# FOTA_MicroController.net
KiCad netlist of a schematic drawn in Altium Designer
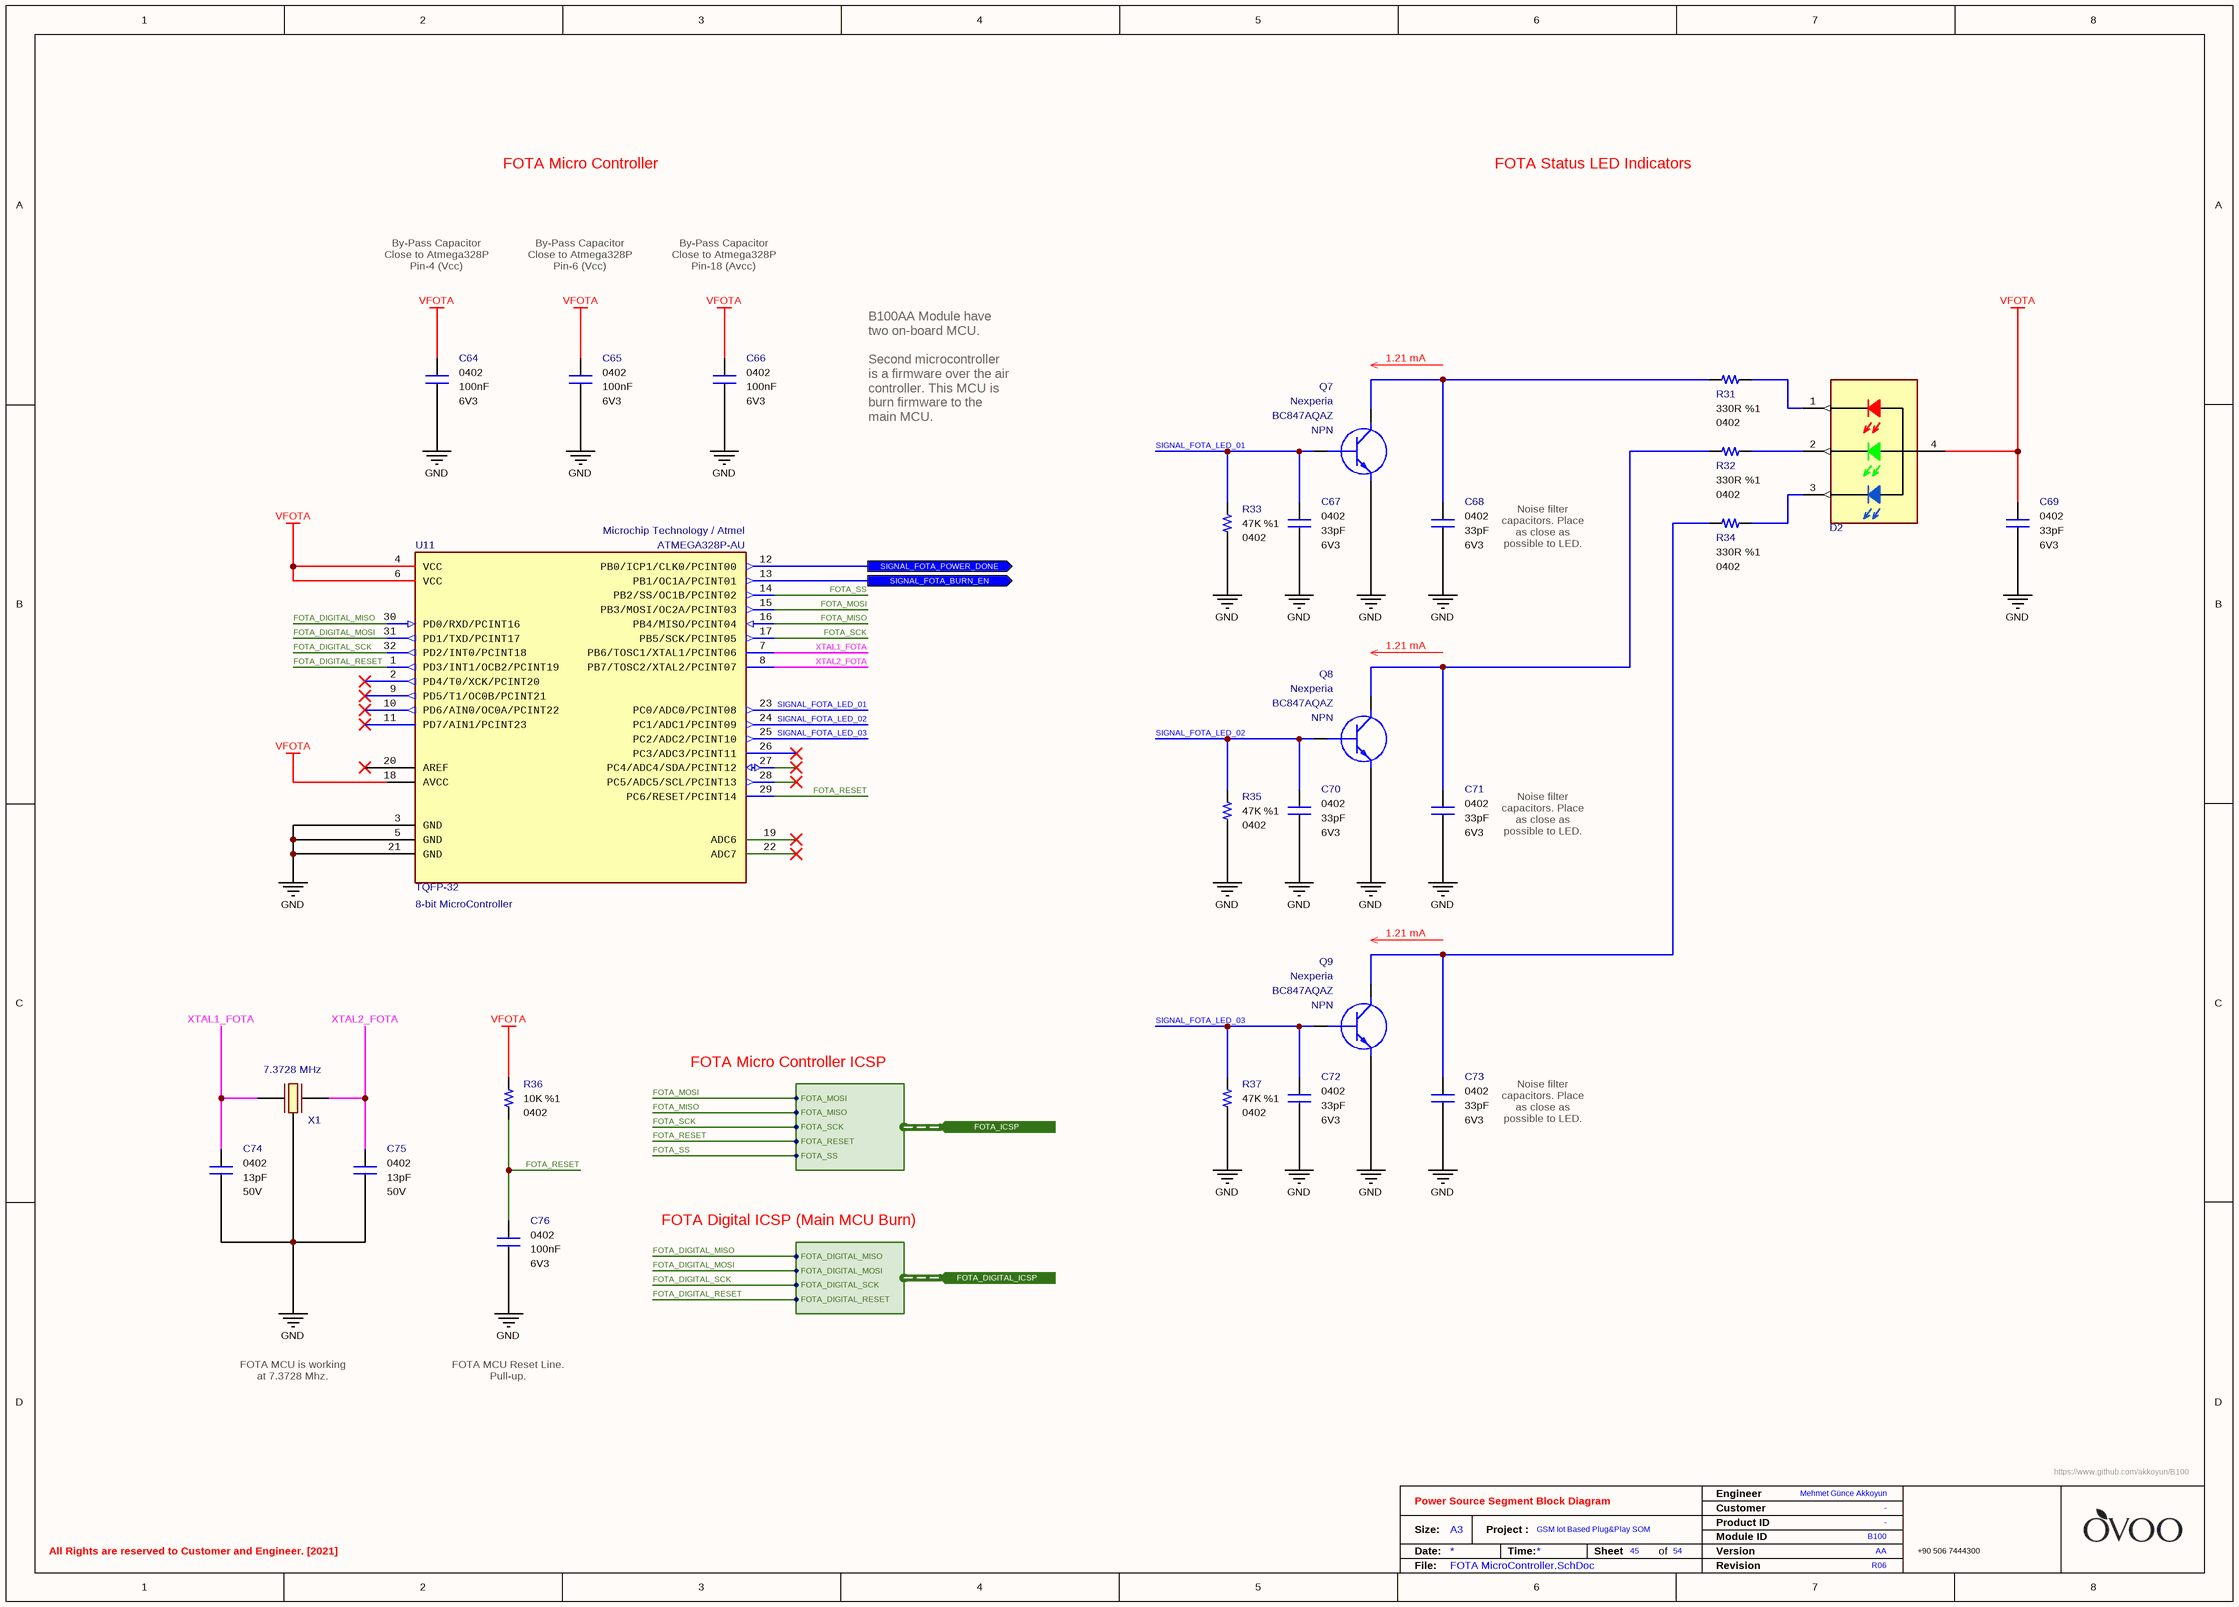
[diagram p0: FOTA MicroController.SchDoc]

(export (version "E")
  (design (tool "Eeschema 10.0.6"))
  (components
    (comp (ref "C64")
      (value "100nF")
      (footprint "CAPACITOR_0402")
      (description "Capacitor - 100nF [0402-6V3] (Ceramic)")
      (fields
        (field (name "TOLERANCE") "%10")
        (field (name "CASE") "0402")
        (field (name "VOLTAGE") "6V3")
        (field (name "MANUFACTURER PART NUMBER") "04026D104KAT4A")
      )
      (libsource (lib "Ovoo_Library") (part "Capacitor - 100nF [0402-6V3]"))
    )
    (comp (ref "C65")
      (value "100nF")
      (footprint "CAPACITOR_0402")
      (description "Capacitor - 100nF [0402-6V3] (Ceramic)")
      (fields
        (field (name "TOLERANCE") "%10")
        (field (name "CASE") "0402")
        (field (name "VOLTAGE") "6V3")
        (field (name "MANUFACTURER PART NUMBER") "04026D104KAT4A")
      )
      (libsource (lib "Ovoo_Library") (part "Capacitor - 100nF [0402-6V3]"))
    )
    (comp (ref "C66")
      (value "100nF")
      (footprint "CAPACITOR_0402")
      (description "Capacitor - 100nF [0402-6V3] (Ceramic)")
      (fields
        (field (name "TOLERANCE") "%10")
        (field (name "CASE") "0402")
        (field (name "VOLTAGE") "6V3")
        (field (name "MANUFACTURER PART NUMBER") "04026D104KAT4A")
      )
      (libsource (lib "Ovoo_Library") (part "Capacitor - 100nF [0402-6V3]"))
    )
    (comp (ref "C67")
      (value "33pF")
      (footprint "CAPACITOR_0402")
      (description "Capacitor - 33pF [0402] (Ceramic)")
      (fields
        (field (name "CASE") "0402")
        (field (name "TOLERANCE") "10%")
        (field (name "VOLTAGE") "6V3")
        (field (name "MANUFACTURER PART NUMBER") "C0402C330J9RACAUTO")
      )
      (libsource (lib "Ovoo_Library") (part "Capacitor - 33pF [0402-6V3]"))
    )
    (comp (ref "C68")
      (value "33pF")
      (footprint "CAPACITOR_0402")
      (description "Capacitor - 33pF [0402] (Ceramic)")
      (fields
        (field (name "CASE") "0402")
        (field (name "TOLERANCE") "10%")
        (field (name "VOLTAGE") "6V3")
        (field (name "MANUFACTURER PART NUMBER") "C0402C330J9RACAUTO")
      )
      (libsource (lib "Ovoo_Library") (part "Capacitor - 33pF [0402-6V3]"))
    )
    (comp (ref "C69")
      (value "33pF")
      (footprint "CAPACITOR_0402")
      (description "Capacitor - 33pF [0402] (Ceramic)")
      (fields
        (field (name "CASE") "0402")
        (field (name "TOLERANCE") "10%")
        (field (name "VOLTAGE") "6V3")
        (field (name "MANUFACTURER PART NUMBER") "C0402C330J9RACAUTO")
      )
      (libsource (lib "Ovoo_Library") (part "Capacitor - 33pF [0402-6V3]"))
    )
    (comp (ref "C70")
      (value "33pF")
      (footprint "CAPACITOR_0402")
      (description "Capacitor - 33pF [0402] (Ceramic)")
      (fields
        (field (name "CASE") "0402")
        (field (name "TOLERANCE") "10%")
        (field (name "VOLTAGE") "6V3")
        (field (name "MANUFACTURER PART NUMBER") "C0402C330J9RACAUTO")
      )
      (libsource (lib "Ovoo_Library") (part "Capacitor - 33pF [0402-6V3]"))
    )
    (comp (ref "C71")
      (value "33pF")
      (footprint "CAPACITOR_0402")
      (description "Capacitor - 33pF [0402] (Ceramic)")
      (fields
        (field (name "CASE") "0402")
        (field (name "TOLERANCE") "10%")
        (field (name "VOLTAGE") "6V3")
        (field (name "MANUFACTURER PART NUMBER") "C0402C330J9RACAUTO")
      )
      (libsource (lib "Ovoo_Library") (part "Capacitor - 33pF [0402-6V3]"))
    )
    (comp (ref "C72")
      (value "33pF")
      (footprint "CAPACITOR_0402")
      (description "Capacitor - 33pF [0402] (Ceramic)")
      (fields
        (field (name "CASE") "0402")
        (field (name "TOLERANCE") "10%")
        (field (name "VOLTAGE") "6V3")
        (field (name "MANUFACTURER PART NUMBER") "C0402C330J9RACAUTO")
      )
      (libsource (lib "Ovoo_Library") (part "Capacitor - 33pF [0402-6V3]"))
    )
    (comp (ref "C73")
      (value "33pF")
      (footprint "CAPACITOR_0402")
      (description "Capacitor - 33pF [0402] (Ceramic)")
      (fields
        (field (name "CASE") "0402")
        (field (name "TOLERANCE") "10%")
        (field (name "VOLTAGE") "6V3")
        (field (name "MANUFACTURER PART NUMBER") "C0402C330J9RACAUTO")
      )
      (libsource (lib "Ovoo_Library") (part "Capacitor - 33pF [0402-6V3]"))
    )
    (comp (ref "C74")
      (value "13pF")
      (footprint "CAPACITOR_0402")
      (description "Capacitor - 13pF [0402] (Ceramic)")
      (fields
        (field (name "TOLERANCE") "1%")
        (field (name "VOLTAGE") "50V")
        (field (name "CASE") "0402")
        (field (name "MANUFACTURER PART NUMBER") "CBR04C130F5GAC")
      )
      (libsource (lib "Ovoo_Library") (part "Capacitor - 13pF [0402-50V]"))
    )
    (comp (ref "C75")
      (value "13pF")
      (footprint "CAPACITOR_0402")
      (description "Capacitor - 13pF [0402] (Ceramic)")
      (fields
        (field (name "TOLERANCE") "1%")
        (field (name "VOLTAGE") "50V")
        (field (name "CASE") "0402")
        (field (name "MANUFACTURER PART NUMBER") "CBR04C130F5GAC")
      )
      (libsource (lib "Ovoo_Library") (part "Capacitor - 13pF [0402-50V]"))
    )
    (comp (ref "C76")
      (value "100nF")
      (footprint "CAPACITOR_0402")
      (description "Capacitor - 100nF [0402-6V3] (Ceramic)")
      (fields
        (field (name "TOLERANCE") "%10")
        (field (name "CASE") "0402")
        (field (name "VOLTAGE") "6V3")
        (field (name "MANUFACTURER PART NUMBER") "04026D104KAT4A")
      )
      (libsource (lib "Ovoo_Library") (part "Capacitor - 100nF [0402-6V3]"))
    )
    (comp (ref "D2")
      (value "150066M153000")
      (footprint "Wurth_0606")
      (description "Standard LEDs - SMD PICOLED series Red LED")
      (fields (field (name "MOUSER PART NUMBER") "710-150066M153000"))
      (libsource (lib "Ovoo_Library") (part "Diode - RGB LED (150066M153000)"))
    )
    (comp (ref "Q7")
      (value "Bipolar NPN Transistors")
      (footprint "SOT1215")
      (description "Bipolar Transistors - BJT BC847AQA/DFN1010D-3/REEL 7\" Q2")
      (fields
        (field (name "MOUSER_PART_NUMBER") "771-BC847AQAZ")
        (field (name "MANUFACTURER_NAME") "Nexperia")
        (field (name "MANUFACTURER_PART_NUMBER") "BC847AQAZ")
        (field (name "POLARITY") "NPN")
      )
      (libsource (lib "Ovoo_Library") (part "Transistor - BC847"))
    )
    (comp (ref "Q8")
      (value "Bipolar NPN Transistors")
      (footprint "SOT1215")
      (description "Bipolar Transistors - BJT BC847AQA/DFN1010D-3/REEL 7\" Q2")
      (fields
        (field (name "MOUSER_PART_NUMBER") "771-BC847AQAZ")
        (field (name "MANUFACTURER_NAME") "Nexperia")
        (field (name "MANUFACTURER_PART_NUMBER") "BC847AQAZ")
        (field (name "POLARITY") "NPN")
      )
      (libsource (lib "Ovoo_Library") (part "Transistor - BC847"))
    )
    (comp (ref "Q9")
      (value "Bipolar NPN Transistors")
      (footprint "SOT1215")
      (description "Bipolar Transistors - BJT BC847AQA/DFN1010D-3/REEL 7\" Q2")
      (fields
        (field (name "MOUSER_PART_NUMBER") "771-BC847AQAZ")
        (field (name "MANUFACTURER_NAME") "Nexperia")
        (field (name "MANUFACTURER_PART_NUMBER") "BC847AQAZ")
        (field (name "POLARITY") "NPN")
      )
      (libsource (lib "Ovoo_Library") (part "Transistor - BC847"))
    )
    (comp (ref "R31")
      (value "330R")
      (footprint "RESISTOR_0402")
      (description "Thick Film Resistors - SMD 1/16 W 330 Ohm 1%")
      (fields
        (field (name "TOLERANCE") "%1")
        (field (name "CASE") "0402")
        (field (name "MANUFACTURER PART NUMBER") "CRCW0402330RFKED")
        (field (name "MOUSER PART NUMBER") "71-CRCW0402-330-E3")
      )
      (libsource (lib "Ovoo_Library") (part "Resistor - 330R"))
    )
    (comp (ref "R32")
      (value "330R")
      (footprint "RESISTOR_0402")
      (description "Thick Film Resistors - SMD 1/16 W 330 Ohm 1%")
      (fields
        (field (name "TOLERANCE") "%1")
        (field (name "CASE") "0402")
        (field (name "MANUFACTURER PART NUMBER") "CRCW0402330RFKED")
        (field (name "MOUSER PART NUMBER") "71-CRCW0402-330-E3")
      )
      (libsource (lib "Ovoo_Library") (part "Resistor - 330R"))
    )
    (comp (ref "R33")
      (value "47K")
      (footprint "RESISTOR_0402")
      (description "Thick Film Resistors - SMD 1/16 W 47 Kohms 1%")
      (fields
        (field (name "TOLERANCE") "%1")
        (field (name "CASE") "0402")
        (field (name "MANUFACTURER PART NUMBER") "CRCW040247K0FKED")
        (field (name "MOUSER PART NUMBER") "71-CRCW0402-47K-E3")
      )
      (libsource (lib "Ovoo_Library") (part "Resistor - 47K"))
    )
    (comp (ref "R34")
      (value "330R")
      (footprint "RESISTOR_0402")
      (description "Thick Film Resistors - SMD 1/16 W 330 Ohm 1%")
      (fields
        (field (name "TOLERANCE") "%1")
        (field (name "CASE") "0402")
        (field (name "MANUFACTURER PART NUMBER") "CRCW0402330RFKED")
        (field (name "MOUSER PART NUMBER") "71-CRCW0402-330-E3")
      )
      (libsource (lib "Ovoo_Library") (part "Resistor - 330R"))
    )
    (comp (ref "R35")
      (value "47K")
      (footprint "RESISTOR_0402")
      (description "Thick Film Resistors - SMD 1/16 W 47 Kohms 1%")
      (fields
        (field (name "TOLERANCE") "%1")
        (field (name "CASE") "0402")
        (field (name "MANUFACTURER PART NUMBER") "CRCW040247K0FKED")
        (field (name "MOUSER PART NUMBER") "71-CRCW0402-47K-E3")
      )
      (libsource (lib "Ovoo_Library") (part "Resistor - 47K"))
    )
    (comp (ref "R36")
      (value "10K")
      (footprint "RESISTOR_0402")
      (description "Thick Film Resistors - SMD 1/16 W 10 Kohms 1%")
      (fields
        (field (name "TOLERANCE") "%1")
        (field (name "CASE") "0402")
        (field (name "MANUFACTURER PART NUMBER") "CRCW040210K0FKED")
        (field (name "MOUSER PART NUMBER") "71-CRCW0402-10K-E3")
      )
      (libsource (lib "Ovoo_Library") (part "Resistor - 10K"))
    )
    (comp (ref "R37")
      (value "47K")
      (footprint "RESISTOR_0402")
      (description "Thick Film Resistors - SMD 1/16 W 47 Kohms 1%")
      (fields
        (field (name "TOLERANCE") "%1")
        (field (name "CASE") "0402")
        (field (name "MANUFACTURER PART NUMBER") "CRCW040247K0FKED")
        (field (name "MOUSER PART NUMBER") "71-CRCW0402-47K-E3")
      )
      (libsource (lib "Ovoo_Library") (part "Resistor - 47K"))
    )
    (comp (ref "U11")
      (value "8-bit MicroController")
      (footprint "TQFP32")
      (description "8-bit Microcontrollers - MCU 32KB In-system Flash 20MHz 1.8V-5.5V")
      (fields
        (field (name "CASE") "TQFP-32")
        (field (name "MOUSER PART NUMBER") "556-ATMEGA328P-AU")
        (field (name "MANUFACTURER PART NUMBER") "ATMEGA328P-AU")
        (field (name "MANUFACTURER NAME") "Microchip Technology / Atmel")
      )
      (libsource (lib "Ovoo_Library") (part "IC - ATMEGA328P"))
    )
    (comp (ref "X1")
      (value "7.3728 MHz")
      (footprint "ABRACON_CRYSTAL")
      (description "Crystals 7.3728MHz 18pF -40C +85C")
      (fields
        (field (name "TOLERANCE") "20 ppm")
        (field (name "MANUFACTURER PART NUMBER") "ABMM2-7.3728MHZ-E2-T")
      )
      (libsource (lib "Ovoo_Library") (part "Crystal - 7.3728 MHz (Abracon)"))
    )
  )
  (nets
    (net (code "3") (name "/FOTA_DIGITAL_MISO") (class "Default")
      (node (ref "U11") (pin "30") (pinfunction "PD0/RXD/PCINT16_30") (pintype "input"))
    )
    (net (code "4") (name "/FOTA_DIGITAL_MOSI") (class "Default")
      (node (ref "U11") (pin "31") (pinfunction "PD1/TXD/PCINT17_31") (pintype "output"))
    )
    (net (code "5") (name "/FOTA_DIGITAL_RESET") (class "Default")
      (node (ref "U11") (pin "1") (pinfunction "PD3/INT1/OCB2/PCINT19_1") (pintype "output"))
    )
    (net (code "6") (name "/FOTA_DIGITAL_SCK") (class "Default")
      (node (ref "U11") (pin "32") (pinfunction "PD2/INT0/PCINT18_32") (pintype "output"))
    )
    (net (code "7") (name "/FOTA_MISO") (class "Default")
      (node (ref "U11") (pin "16") (pinfunction "PB4/MISO/PCINT04_16") (pintype "input"))
    )
    (net (code "8") (name "/FOTA_MOSI") (class "Default")
      (node (ref "U11") (pin "15") (pinfunction "PB3/MOSI/OC2A/PCINT03_15") (pintype "output"))
    )
    (net (code "9") (name "/FOTA_RESET") (class "Default")
      (node (ref "C76") (pin "2") (pinfunction "2_2") (pintype "passive"))
      (node (ref "R36") (pin "1") (pinfunction "1_1") (pintype "passive"))
      (node (ref "U11") (pin "29") (pinfunction "PC6/RESET/PCINT14_29") (pintype "passive"))
    )
    (net (code "10") (name "/FOTA_SCK") (class "Default")
      (node (ref "U11") (pin "17") (pinfunction "PB5/SCK/PCINT05_17") (pintype "output"))
    )
    (net (code "11") (name "/FOTA_SS") (class "Default")
      (node (ref "U11") (pin "14") (pinfunction "PB2/SS/OC1B/PCINT02_14") (pintype "output"))
    )
    (net (code "12") (name "/SIGNAL_FOTA_BURN_EN") (class "Default")
      (node (ref "U11") (pin "13") (pinfunction "PB1/OC1A/PCINT01_13") (pintype "output"))
    )
    (net (code "13") (name "/SIGNAL_FOTA_LED_01") (class "Default")
      (node (ref "C67") (pin "1") (pinfunction "1_1") (pintype "passive"))
      (node (ref "Q7") (pin "1") (pinfunction "B_1") (pintype "passive"))
      (node (ref "R33") (pin "2") (pinfunction "2_2") (pintype "passive"))
      (node (ref "U11") (pin "23") (pinfunction "PC0/ADC0/PCINT08_23") (pintype "output"))
    )
    (net (code "14") (name "/SIGNAL_FOTA_LED_02") (class "Default")
      (node (ref "C70") (pin "1") (pinfunction "1_1") (pintype "passive"))
      (node (ref "Q8") (pin "1") (pinfunction "B_1") (pintype "passive"))
      (node (ref "R35") (pin "2") (pinfunction "2_2") (pintype "passive"))
      (node (ref "U11") (pin "24") (pinfunction "PC1/ADC1/PCINT09_24") (pintype "output"))
    )
    (net (code "15") (name "/SIGNAL_FOTA_LED_03") (class "Default")
      (node (ref "C72") (pin "1") (pinfunction "1_1") (pintype "passive"))
      (node (ref "Q9") (pin "1") (pinfunction "B_1") (pintype "passive"))
      (node (ref "R37") (pin "2") (pinfunction "2_2") (pintype "passive"))
      (node (ref "U11") (pin "25") (pinfunction "PC2/ADC2/PCINT10_25") (pintype "output"))
    )
    (net (code "16") (name "/SIGNAL_FOTA_POWER_DONE") (class "Default")
      (node (ref "U11") (pin "12") (pinfunction "PB0/ICP1/CLK0/PCINT00_12") (pintype "output"))
    )
    (net (code "17") (name "/XTAL1_FOTA") (class "Default")
      (node (ref "C74") (pin "2") (pinfunction "2_2") (pintype "passive"))
      (node (ref "U11") (pin "7") (pinfunction "PB6/TOSC1/XTAL1/PCINT06_7") (pintype "passive"))
      (node (ref "X1") (pin "3") (pinfunction "OUT/IN_3") (pintype "passive"))
    )
    (net (code "18") (name "/XTAL2_FOTA") (class "Default")
      (node (ref "C75") (pin "2") (pinfunction "2_2") (pintype "passive"))
      (node (ref "U11") (pin "8") (pinfunction "PB7/TOSC2/XTAL2/PCINT07_8") (pintype "passive"))
      (node (ref "X1") (pin "1") (pinfunction "IN/OUT_1") (pintype "passive"))
    )
    (net (code "21") (name "GND") (class "Default")
      (node (ref "C64") (pin "1") (pinfunction "1_1") (pintype "passive"))
      (node (ref "C65") (pin "1") (pinfunction "1_1") (pintype "passive"))
      (node (ref "C66") (pin "1") (pinfunction "1_1") (pintype "passive"))
      (node (ref "C67") (pin "2") (pinfunction "2_2") (pintype "passive"))
      (node (ref "C68") (pin "2") (pinfunction "2_2") (pintype "passive"))
      (node (ref "C69") (pin "2") (pinfunction "2_2") (pintype "passive"))
      (node (ref "C70") (pin "2") (pinfunction "2_2") (pintype "passive"))
      (node (ref "C71") (pin "2") (pinfunction "2_2") (pintype "passive"))
      (node (ref "C72") (pin "2") (pinfunction "2_2") (pintype "passive"))
      (node (ref "C73") (pin "2") (pinfunction "2_2") (pintype "passive"))
      (node (ref "C74") (pin "1") (pinfunction "1_1") (pintype "passive"))
      (node (ref "C75") (pin "1") (pinfunction "1_1") (pintype "passive"))
      (node (ref "C76") (pin "1") (pinfunction "1_1") (pintype "passive"))
      (node (ref "Q7") (pin "2") (pinfunction "E_2") (pintype "passive"))
      (node (ref "Q8") (pin "2") (pinfunction "E_2") (pintype "passive"))
      (node (ref "Q9") (pin "2") (pinfunction "E_2") (pintype "passive"))
      (node (ref "R33") (pin "1") (pinfunction "1_1") (pintype "passive"))
      (node (ref "R35") (pin "1") (pinfunction "1_1") (pintype "passive"))
      (node (ref "R37") (pin "1") (pinfunction "1_1") (pintype "passive"))
      (node (ref "U11") (pin "21") (pinfunction "GND_21") (pintype "power_in"))
      (node (ref "U11") (pin "3") (pinfunction "GND_3") (pintype "power_in"))
      (node (ref "U11") (pin "5") (pinfunction "GND_5") (pintype "power_in"))
      (node (ref "X1") (pin "2") (pinfunction "GND_2") (pintype "passive"))
    )
    (net (code "22") (name "Net-(D2-Pad1)") (class "Default")
      (node (ref "D2") (pin "1") (pinfunction "1_1") (pintype "output"))
      (node (ref "R31") (pin "2") (pinfunction "2_2") (pintype "passive"))
    )
    (net (code "23") (name "Net-(D2-Pad2)") (class "Default")
      (node (ref "D2") (pin "2") (pinfunction "2_2") (pintype "output"))
      (node (ref "R32") (pin "2") (pinfunction "2_2") (pintype "passive"))
    )
    (net (code "24") (name "Net-(D2-Pad3)") (class "Default")
      (node (ref "D2") (pin "3") (pinfunction "3_3") (pintype "output"))
      (node (ref "R34") (pin "2") (pinfunction "2_2") (pintype "passive"))
    )
    (net (code "25") (name "Net-(Q7-C)") (class "Default")
      (node (ref "C68") (pin "1") (pinfunction "1_1") (pintype "passive"))
      (node (ref "Q7") (pin "3") (pinfunction "C_3") (pintype "passive"))
      (node (ref "R31") (pin "1") (pinfunction "1_1") (pintype "passive"))
    )
    (net (code "26") (name "Net-(Q8-C)") (class "Default")
      (node (ref "C71") (pin "1") (pinfunction "1_1") (pintype "passive"))
      (node (ref "Q8") (pin "3") (pinfunction "C_3") (pintype "passive"))
      (node (ref "R32") (pin "1") (pinfunction "1_1") (pintype "passive"))
    )
    (net (code "27") (name "Net-(Q9-C)") (class "Default")
      (node (ref "C73") (pin "1") (pinfunction "1_1") (pintype "passive"))
      (node (ref "Q9") (pin "3") (pinfunction "C_3") (pintype "passive"))
      (node (ref "R34") (pin "1") (pinfunction "1_1") (pintype "passive"))
    )
    (net (code "28") (name "VFOTA") (class "Default")
      (node (ref "C64") (pin "2") (pinfunction "2_2") (pintype "passive"))
      (node (ref "C65") (pin "2") (pinfunction "2_2") (pintype "passive"))
      (node (ref "C66") (pin "2") (pinfunction "2_2") (pintype "passive"))
      (node (ref "C69") (pin "1") (pinfunction "1_1") (pintype "passive"))
      (node (ref "D2") (pin "4") (pinfunction "4_4") (pintype "power_in"))
      (node (ref "R36") (pin "2") (pinfunction "2_2") (pintype "passive"))
      (node (ref "U11") (pin "18") (pinfunction "AVCC_18") (pintype "passive"))
      (node (ref "U11") (pin "4") (pinfunction "VCC_4") (pintype "power_in"))
      (node (ref "U11") (pin "6") (pinfunction "VCC_6") (pintype "power_in"))
    )
    (net (code "29") (name "unconnected-(U11-ADC6-Pad19)") (class "Default")
      (node (ref "U11") (pin "19") (pinfunction "ADC6_19") (pintype "passive+no_connect"))
    )
    (net (code "30") (name "unconnected-(U11-ADC7-Pad22)") (class "Default")
      (node (ref "U11") (pin "22") (pinfunction "ADC7_22") (pintype "passive+no_connect"))
    )
    (net (code "31") (name "unconnected-(U11-AREF-Pad20)") (class "Default")
      (node (ref "U11") (pin "20") (pinfunction "AREF_20") (pintype "passive+no_connect"))
    )
    (net (code "32") (name "unconnected-(U11-PC3{slash}ADC3{slash}PCINT11-Pad26)") (class "Default")
      (node (ref "U11") (pin "26") (pinfunction "PC3/ADC3/PCINT11_26") (pintype "passive+no_connect"))
    )
    (net (code "33") (name "unconnected-(U11-PC4{slash}ADC4{slash}SDA{slash}PCINT12-Pad27)") (class "Default")
      (node (ref "U11") (pin "27") (pinfunction "PC4/ADC4/SDA/PCINT12_27") (pintype "bidirectional+no_connect"))
    )
    (net (code "34") (name "unconnected-(U11-PC5{slash}ADC5{slash}SCL{slash}PCINT13-Pad28)") (class "Default")
      (node (ref "U11") (pin "28") (pinfunction "PC5/ADC5/SCL/PCINT13_28") (pintype "output+no_connect"))
    )
    (net (code "35") (name "unconnected-(U11-PD4{slash}T0{slash}XCK{slash}PCINT20-Pad2)") (class "Default")
      (node (ref "U11") (pin "2") (pinfunction "PD4/T0/XCK/PCINT20_2") (pintype "output+no_connect"))
    )
    (net (code "36") (name "unconnected-(U11-PD5{slash}T1{slash}OC0B{slash}PCINT21-Pad9)") (class "Default")
      (node (ref "U11") (pin "9") (pinfunction "PD5/T1/OC0B/PCINT21_9") (pintype "output+no_connect"))
    )
    (net (code "37") (name "unconnected-(U11-PD6{slash}AIN0{slash}OC0A{slash}PCINT22-Pad10)") (class "Default")
      (node (ref "U11") (pin "10") (pinfunction "PD6/AIN0/OC0A/PCINT22_10") (pintype "output+no_connect"))
    )
    (net (code "38") (name "unconnected-(U11-PD7{slash}AIN1{slash}PCINT23-Pad11)") (class "Default")
      (node (ref "U11") (pin "11") (pinfunction "PD7/AIN1/PCINT23_11") (pintype "passive+no_connect"))
    )
    (net (code "39") (name "unconnected-(X1-GND-Pad4)") (class "Default")
      (node (ref "X1") (pin "4") (pinfunction "GND_4") (pintype "passive"))
    )
  )
)
